# SCH_USBASP_AVR_Programmer_module__2021-0.net
KiCad netlist of a schematic drawn in EasyEDA
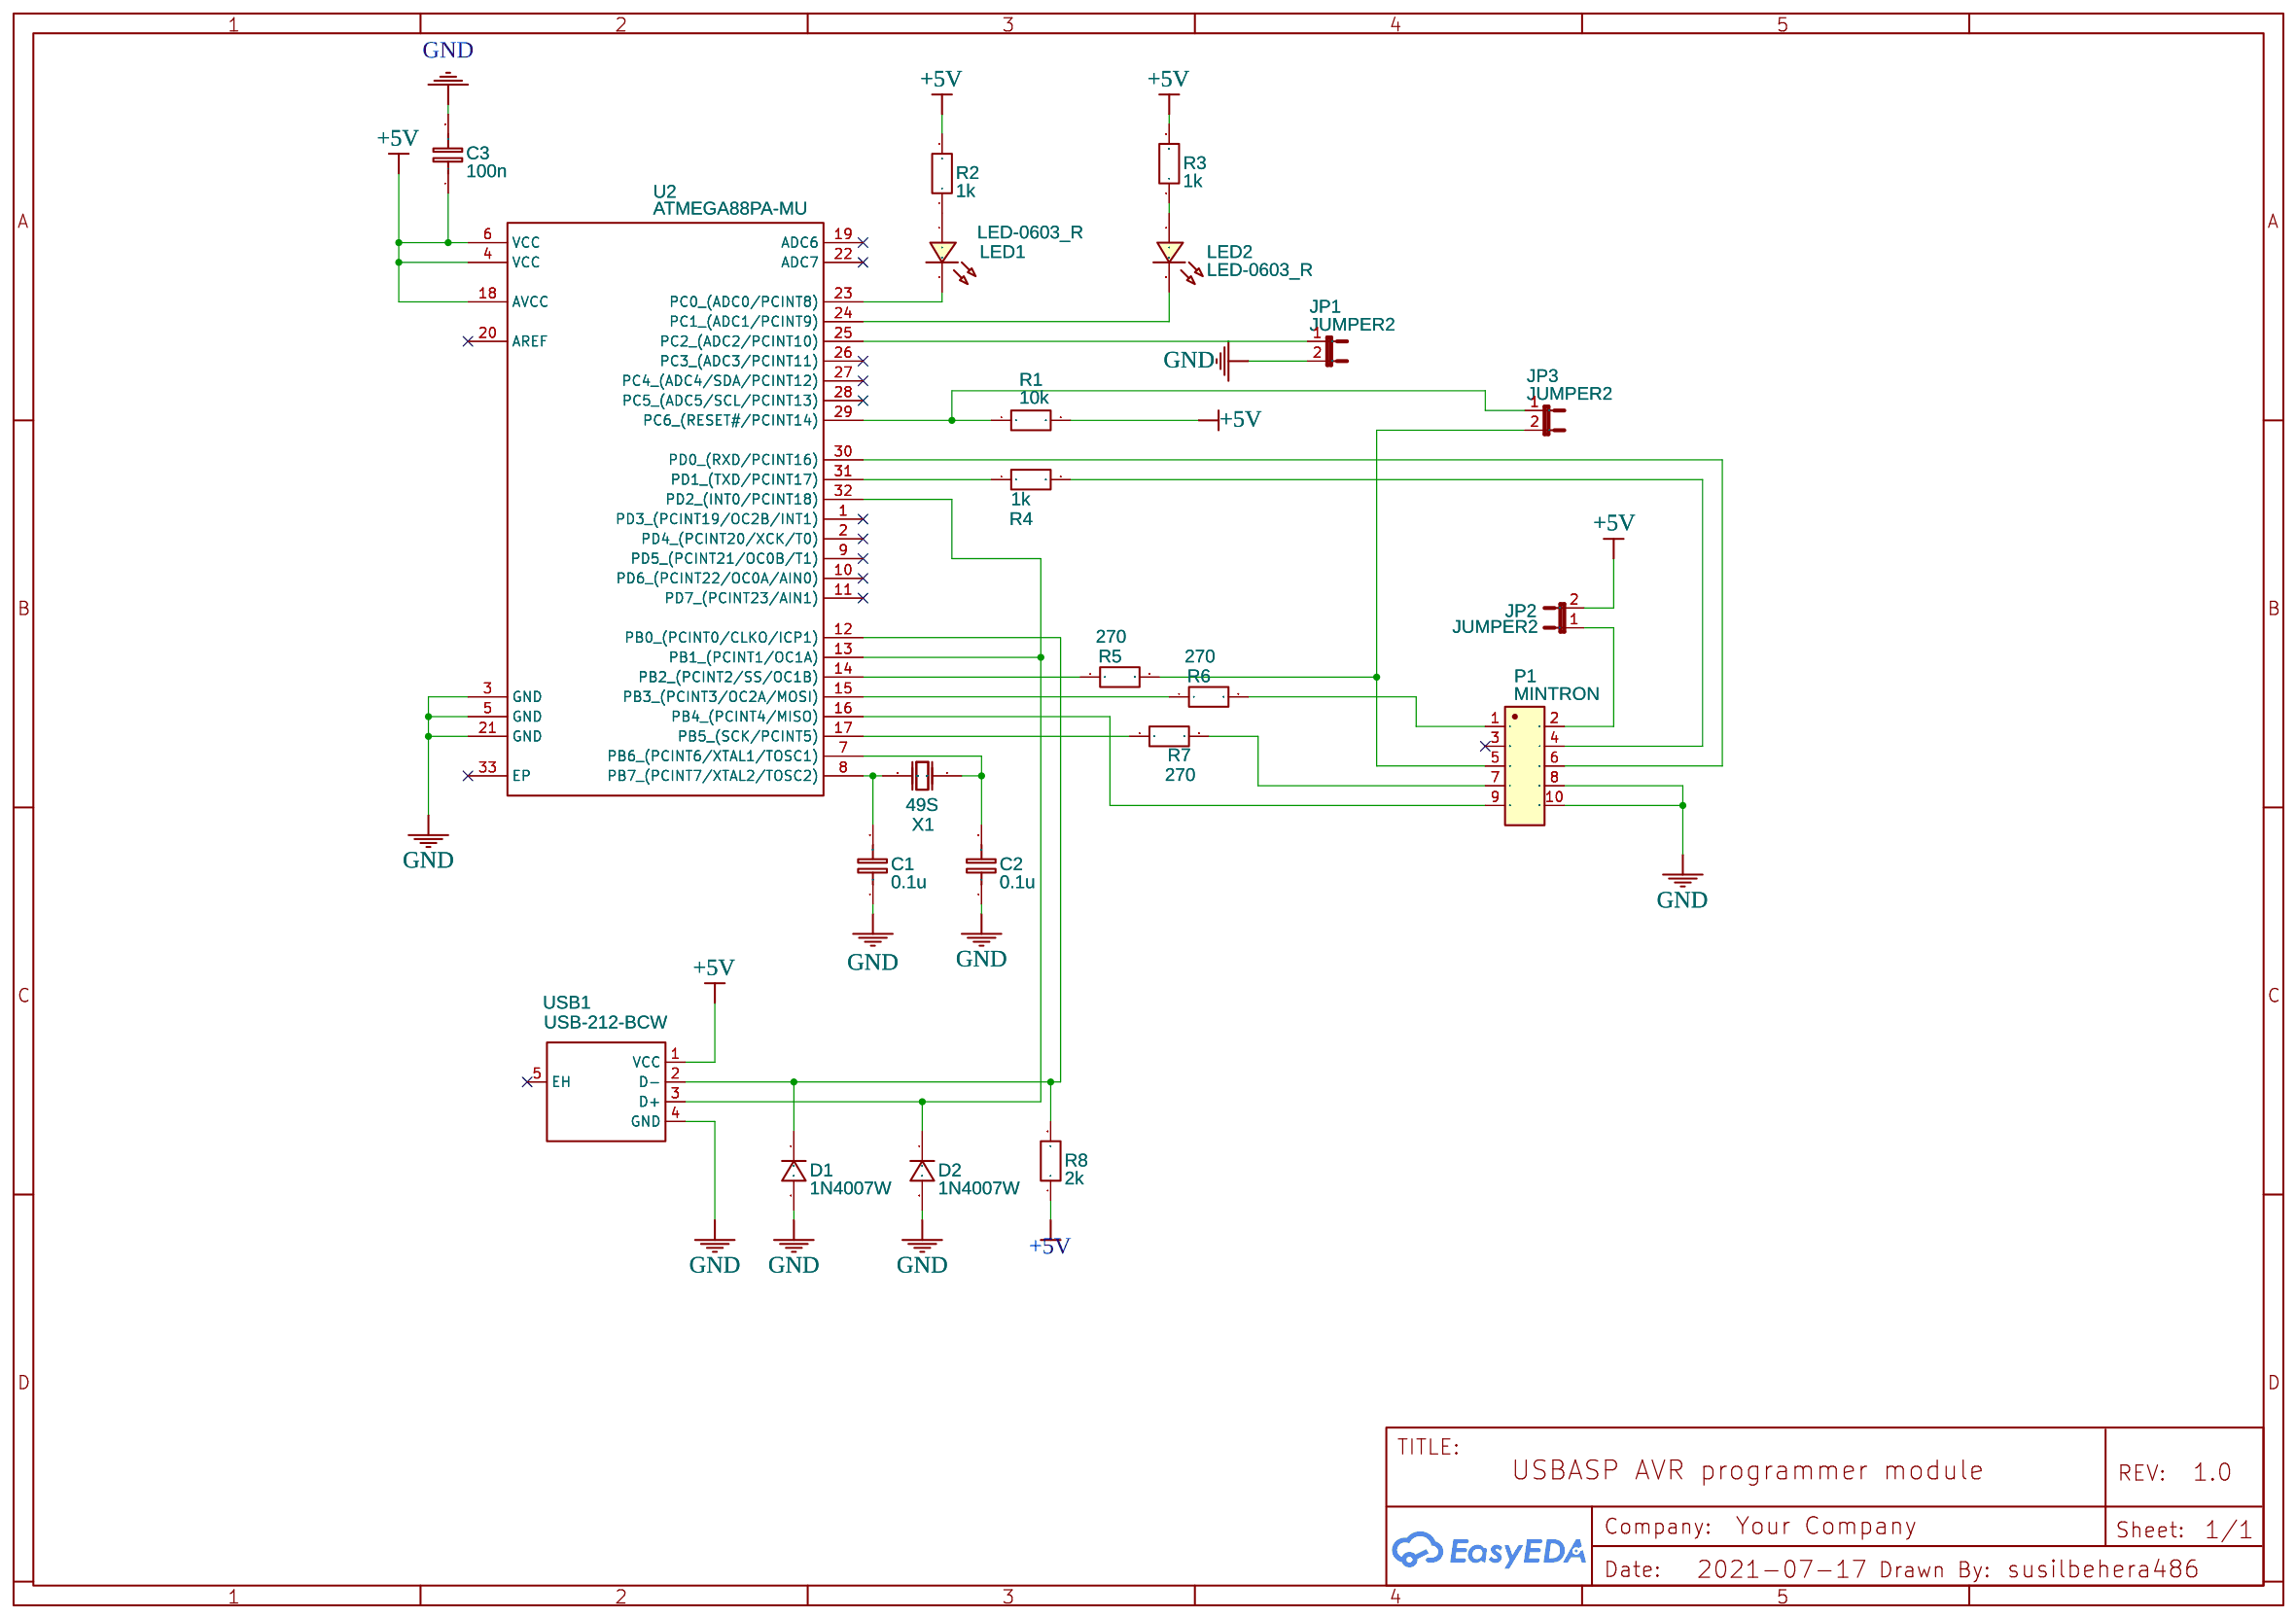
[diagram p0: schematic sheet]

(export (version "E")
  (design (tool "Eeschema 10.0.6"))
  (components
    (comp (ref "C1") (value "0.1u") (libsource (lib "") (part "C_0603_EU")))
    (comp (ref "C2") (value "0.1u") (libsource (lib "") (part "C_0603_EU")))
    (comp (ref "C3") (value "100n") (libsource (lib "") (part "C_0603_EU_1")))
    (comp (ref "D1")
      (value "1N4007W")
      (fields (field (name "BOM_Supplier Part") "C328592"))
      (libsource (lib "") (part "1N4007W"))
    )
    (comp (ref "D2")
      (value "1N4007W")
      (fields (field (name "BOM_Supplier Part") "C328592"))
      (libsource (lib "") (part "1N4007W"))
    )
    (comp (ref "JP1") (value "JUMPER2") (libsource (lib "") (part "JUMPER2")))
    (comp (ref "JP2") (value "JUMPER2") (libsource (lib "") (part "JUMPER2_1")))
    (comp (ref "JP3") (value "JUMPER2") (libsource (lib "") (part "JUMPER2")))
    (comp (ref "LED1")
      (value "LED-0603_R")
      (fields
        (field (name "BOM_Manufacturer Part") "19-217/R6C-AL1M2VY/3T")
        (field (name "BOM_Supplier Part") "C72044")
      )
      (libsource (lib "") (part "LED-0603_R"))
    )
    (comp (ref "LED2")
      (value "LED-0603_R")
      (fields
        (field (name "BOM_Manufacturer Part") "19-217/R6C-AL1M2VY/3T")
        (field (name "BOM_Supplier Part") "C72044")
      )
      (libsource (lib "") (part "LED-0603_R"))
    )
    (comp (ref "P1")
      (value "MINTRON")
      (fields
        (field (name "BOM_Manufacturer Part") "MTB111-10S")
        (field (name "BOM_Supplier Part") "C376112")
      )
      (libsource (lib "") (part "Con2x5"))
    )
    (comp (ref "R1") (value "10k") (libsource (lib "") (part "R_0603_EU")))
    (comp (ref "R2") (value "1k") (libsource (lib "") (part "R_0603_EU_1")))
    (comp (ref "R3") (value "1k") (libsource (lib "") (part "R_0603_EU_1")))
    (comp (ref "R4") (value "1k") (libsource (lib "") (part "R_0603_EU")))
    (comp (ref "R5") (value "270") (libsource (lib "") (part "R_0603_EU")))
    (comp (ref "R6") (value "270") (libsource (lib "") (part "R_0603_EU")))
    (comp (ref "R7") (value "270") (libsource (lib "") (part "R_0603_EU")))
    (comp (ref "R8") (value "2k") (libsource (lib "") (part "R_0603_EU_1")))
    (comp (ref "U2")
      (value "ATMEGA88PA-MU")
      (fields (field (name "BOM_Supplier Part") "C111457"))
      (libsource (lib "") (part "ATMEGA88PA-MU"))
    )
    (comp (ref "USB1")
      (value "USB-212-BCW")
      (fields (field (name "BOM_Supplier Part") "C720521"))
      (libsource (lib "") (part "USB-212-BCW"))
    )
    (comp (ref "X1")
      (value "49S")
      (fields
        (field (name "BOM_Manufacturer Part") "49S DIP Crystal insulation film")
        (field (name "BOM_Supplier Part") "C35018")
      )
      (libsource (lib "") (part "49S DIP Crystal insulation film"))
    )
  )
  (nets
    (net (code "1") (name "+5V") (class "Default")
      (node (ref "C3") (pin "1") (pinfunction "1_1") (pintype "unspecified"))
      (node (ref "JP2") (pin "2") (pinfunction "2_2") (pintype "unspecified"))
      (node (ref "R1") (pin "2") (pinfunction "2_2") (pintype "unspecified"))
      (node (ref "R2") (pin "2") (pinfunction "2_2") (pintype "unspecified"))
      (node (ref "R3") (pin "2") (pinfunction "2_2") (pintype "unspecified"))
      (node (ref "R8") (pin "1") (pinfunction "1_1") (pintype "unspecified"))
      (node (ref "U2") (pin "18") (pinfunction "AVCC_18") (pintype "passive"))
      (node (ref "U2") (pin "4") (pinfunction "VCC_4") (pintype "passive"))
      (node (ref "U2") (pin "6") (pinfunction "VCC_6") (pintype "passive"))
      (node (ref "USB1") (pin "1") (pinfunction "VCC_1") (pintype "input"))
    )
    (net (code "2") (name "GND") (class "Default")
      (node (ref "C1") (pin "1") (pinfunction "1_1") (pintype "unspecified"))
      (node (ref "C2") (pin "1") (pinfunction "1_1") (pintype "unspecified"))
      (node (ref "C3") (pin "2") (pinfunction "2_2") (pintype "unspecified"))
      (node (ref "D1") (pin "2") (pinfunction "2_2") (pintype "unspecified"))
      (node (ref "D2") (pin "2") (pinfunction "2_2") (pintype "unspecified"))
      (node (ref "JP1") (pin "2") (pinfunction "2_2") (pintype "unspecified"))
      (node (ref "P1") (pin "10") (pinfunction "10_10") (pintype "unspecified"))
      (node (ref "P1") (pin "8") (pinfunction "8_8") (pintype "unspecified"))
      (node (ref "U2") (pin "21") (pinfunction "GND_21") (pintype "passive"))
      (node (ref "U2") (pin "3") (pinfunction "GND_3") (pintype "passive"))
      (node (ref "U2") (pin "5") (pinfunction "GND_5") (pintype "passive"))
      (node (ref "USB1") (pin "4") (pinfunction "GND_4") (pintype "input"))
    )
    (net (code "3") (name "Net-(JP2-Pad1)") (class "Default")
      (node (ref "JP2") (pin "1") (pinfunction "1_1") (pintype "unspecified"))
      (node (ref "P1") (pin "2") (pinfunction "2_2") (pintype "unspecified"))
    )
    (net (code "4") (name "Net-(JP3-Pad2)") (class "Default")
      (node (ref "JP3") (pin "2") (pinfunction "2_2") (pintype "unspecified"))
      (node (ref "P1") (pin "5") (pinfunction "5_5") (pintype "unspecified"))
      (node (ref "R5") (pin "2") (pinfunction "2_2") (pintype "unspecified"))
    )
    (net (code "5") (name "Net-(LED1-Pad1)") (class "Default")
      (node (ref "LED1") (pin "1") (pinfunction "1_1") (pintype "unspecified"))
      (node (ref "R2") (pin "1") (pinfunction "1_1") (pintype "unspecified"))
    )
    (net (code "6") (name "Net-(LED2-Pad1)") (class "Default")
      (node (ref "LED2") (pin "1") (pinfunction "1_1") (pintype "unspecified"))
      (node (ref "R3") (pin "1") (pinfunction "1_1") (pintype "unspecified"))
    )
    (net (code "7") (name "Net-(P1-Pad1)") (class "Default")
      (node (ref "P1") (pin "1") (pinfunction "1_1") (pintype "unspecified"))
      (node (ref "R6") (pin "2") (pinfunction "2_2") (pintype "unspecified"))
    )
    (net (code "8") (name "Net-(P1-Pad4)") (class "Default")
      (node (ref "P1") (pin "4") (pinfunction "4_4") (pintype "unspecified"))
      (node (ref "R4") (pin "2") (pinfunction "2_2") (pintype "unspecified"))
    )
    (net (code "9") (name "Net-(P1-Pad7)") (class "Default")
      (node (ref "P1") (pin "7") (pinfunction "7_7") (pintype "unspecified"))
      (node (ref "R7") (pin "2") (pinfunction "2_2") (pintype "unspecified"))
    )
    (net (code "10") (name "Net-(U2-PB0_(PCINT0{slash}CLKO{slash}ICP1))") (class "Default")
      (node (ref "D1") (pin "1") (pinfunction "1_1") (pintype "unspecified"))
      (node (ref "R8") (pin "2") (pinfunction "2_2") (pintype "unspecified"))
      (node (ref "U2") (pin "12") (pinfunction "PB0_(PCINT0/CLKO/ICP1)_12") (pintype "bidirectional"))
      (node (ref "USB1") (pin "2") (pinfunction "D-_2") (pintype "input"))
    )
    (net (code "11") (name "Net-(U2-PB1_(PCINT1{slash}OC1A))") (class "Default")
      (node (ref "D2") (pin "1") (pinfunction "1_1") (pintype "unspecified"))
      (node (ref "U2") (pin "13") (pinfunction "PB1_(PCINT1/OC1A)_13") (pintype "bidirectional"))
      (node (ref "U2") (pin "32") (pinfunction "PD2_(INT0/PCINT18)_32") (pintype "bidirectional"))
      (node (ref "USB1") (pin "3") (pinfunction "D+_3") (pintype "input"))
    )
    (net (code "12") (name "Net-(U2-PB2_(PCINT2{slash}SS{slash}OC1B))") (class "Default")
      (node (ref "R5") (pin "1") (pinfunction "1_1") (pintype "unspecified"))
      (node (ref "U2") (pin "14") (pinfunction "PB2_(PCINT2/SS/OC1B)_14") (pintype "bidirectional"))
    )
    (net (code "13") (name "Net-(U2-PB3_(PCINT3{slash}OC2A{slash}MOSI))") (class "Default")
      (node (ref "R6") (pin "1") (pinfunction "1_1") (pintype "unspecified"))
      (node (ref "U2") (pin "15") (pinfunction "PB3_(PCINT3/OC2A/MOSI)_15") (pintype "bidirectional"))
    )
    (net (code "14") (name "Net-(U2-PB4_(PCINT4{slash}MISO))") (class "Default")
      (node (ref "P1") (pin "9") (pinfunction "9_9") (pintype "unspecified"))
      (node (ref "U2") (pin "16") (pinfunction "PB4_(PCINT4/MISO)_16") (pintype "bidirectional"))
    )
    (net (code "15") (name "Net-(U2-PB5_(SCK{slash}PCINT5))") (class "Default")
      (node (ref "R7") (pin "1") (pinfunction "1_1") (pintype "unspecified"))
      (node (ref "U2") (pin "17") (pinfunction "PB5_(SCK/PCINT5)_17") (pintype "bidirectional"))
    )
    (net (code "16") (name "Net-(U2-PB6_(PCINT6{slash}XTAL1{slash}TOSC1))") (class "Default")
      (node (ref "C2") (pin "2") (pinfunction "2_2") (pintype "unspecified"))
      (node (ref "U2") (pin "7") (pinfunction "PB6_(PCINT6/XTAL1/TOSC1)_7") (pintype "bidirectional"))
      (node (ref "X1") (pin "1") (pinfunction "OSC1_1") (pintype "input"))
    )
    (net (code "17") (name "Net-(U2-PB7_(PCINT7{slash}XTAL2{slash}TOSC2))") (class "Default")
      (node (ref "C1") (pin "2") (pinfunction "2_2") (pintype "unspecified"))
      (node (ref "U2") (pin "8") (pinfunction "PB7_(PCINT7/XTAL2/TOSC2)_8") (pintype "bidirectional"))
      (node (ref "X1") (pin "2") (pinfunction "OSC2_2") (pintype "input"))
    )
    (net (code "18") (name "Net-(U2-PC0_(ADC0{slash}PCINT8))") (class "Default")
      (node (ref "LED1") (pin "2") (pinfunction "2_2") (pintype "unspecified"))
      (node (ref "U2") (pin "23") (pinfunction "PC0_(ADC0/PCINT8)_23") (pintype "bidirectional"))
    )
    (net (code "19") (name "Net-(U2-PC1_(ADC1{slash}PCINT9))") (class "Default")
      (node (ref "LED2") (pin "2") (pinfunction "2_2") (pintype "unspecified"))
      (node (ref "U2") (pin "24") (pinfunction "PC1_(ADC1/PCINT9)_24") (pintype "bidirectional"))
    )
    (net (code "20") (name "Net-(U2-PC2_(ADC2{slash}PCINT10))") (class "Default")
      (node (ref "JP1") (pin "1") (pinfunction "1_1") (pintype "unspecified"))
      (node (ref "U2") (pin "25") (pinfunction "PC2_(ADC2/PCINT10)_25") (pintype "bidirectional"))
    )
    (net (code "21") (name "Net-(U2-PC6_(RESET#{slash}PCINT14))") (class "Default")
      (node (ref "JP3") (pin "1") (pinfunction "1_1") (pintype "unspecified"))
      (node (ref "R1") (pin "1") (pinfunction "1_1") (pintype "unspecified"))
      (node (ref "U2") (pin "29") (pinfunction "PC6_(RESET#/PCINT14)_29") (pintype "bidirectional"))
    )
    (net (code "22") (name "Net-(U2-PD0_(RXD{slash}PCINT16))") (class "Default")
      (node (ref "P1") (pin "6") (pinfunction "6_6") (pintype "unspecified"))
      (node (ref "U2") (pin "30") (pinfunction "PD0_(RXD/PCINT16)_30") (pintype "bidirectional"))
    )
    (net (code "23") (name "Net-(U2-PD1_(TXD{slash}PCINT17))") (class "Default")
      (node (ref "R4") (pin "1") (pinfunction "1_1") (pintype "unspecified"))
      (node (ref "U2") (pin "31") (pinfunction "PD1_(TXD/PCINT17)_31") (pintype "bidirectional"))
    )
    (net (code "24") (name "unconnected-(P1-Pad3)") (class "Default")
      (node (ref "P1") (pin "3") (pinfunction "3_3") (pintype "unspecified+no_connect"))
    )
    (net (code "25") (name "unconnected-(U2-ADC6-Pad19)") (class "Default")
      (node (ref "U2") (pin "19") (pinfunction "ADC6_19") (pintype "input+no_connect"))
    )
    (net (code "26") (name "unconnected-(U2-ADC7-Pad22)") (class "Default")
      (node (ref "U2") (pin "22") (pinfunction "ADC7_22") (pintype "input+no_connect"))
    )
    (net (code "27") (name "unconnected-(U2-AREF-Pad20)") (class "Default")
      (node (ref "U2") (pin "20") (pinfunction "AREF_20") (pintype "unspecified+no_connect"))
    )
    (net (code "28") (name "unconnected-(U2-EP-Pad33)") (class "Default")
      (node (ref "U2") (pin "33") (pinfunction "EP_33") (pintype "passive+no_connect"))
    )
    (net (code "29") (name "unconnected-(U2-PC3_(ADC3{slash}PCINT11)-Pad26)") (class "Default")
      (node (ref "U2") (pin "26") (pinfunction "PC3_(ADC3/PCINT11)_26") (pintype "bidirectional+no_connect"))
    )
    (net (code "30") (name "unconnected-(U2-PC4_(ADC4{slash}SDA{slash}PCINT12)-Pad27)") (class "Default")
      (node (ref "U2") (pin "27") (pinfunction "PC4_(ADC4/SDA/PCINT12)_27") (pintype "bidirectional+no_connect"))
    )
    (net (code "31") (name "unconnected-(U2-PC5_(ADC5{slash}SCL{slash}PCINT13)-Pad28)") (class "Default")
      (node (ref "U2") (pin "28") (pinfunction "PC5_(ADC5/SCL/PCINT13)_28") (pintype "bidirectional+no_connect"))
    )
    (net (code "32") (name "unconnected-(U2-PD3_(PCINT19{slash}OC2B{slash}INT1)-Pad1)") (class "Default")
      (node (ref "U2") (pin "1") (pinfunction "PD3_(PCINT19/OC2B/INT1)_1") (pintype "bidirectional+no_connect"))
    )
    (net (code "33") (name "unconnected-(U2-PD4_(PCINT20{slash}XCK{slash}T0)-Pad2)") (class "Default")
      (node (ref "U2") (pin "2") (pinfunction "PD4_(PCINT20/XCK/T0)_2") (pintype "bidirectional+no_connect"))
    )
    (net (code "34") (name "unconnected-(U2-PD5_(PCINT21{slash}OC0B{slash}T1)-Pad9)") (class "Default")
      (node (ref "U2") (pin "9") (pinfunction "PD5_(PCINT21/OC0B/T1)_9") (pintype "bidirectional+no_connect"))
    )
    (net (code "35") (name "unconnected-(U2-PD6_(PCINT22{slash}OC0A{slash}AIN0)-Pad10)") (class "Default")
      (node (ref "U2") (pin "10") (pinfunction "PD6_(PCINT22/OC0A/AIN0)_10") (pintype "bidirectional+no_connect"))
    )
    (net (code "36") (name "unconnected-(U2-PD7_(PCINT23{slash}AIN1)-Pad11)") (class "Default")
      (node (ref "U2") (pin "11") (pinfunction "PD7_(PCINT23/AIN1)_11") (pintype "bidirectional+no_connect"))
    )
    (net (code "37") (name "unconnected-(USB1-EH-Pad5)") (class "Default")
      (node (ref "USB1") (pin "5") (pinfunction "EH_5") (pintype "unspecified+no_connect"))
    )
  )
)
